# bbps.net
KiCad netlist of a schematic drawn in EAGLE
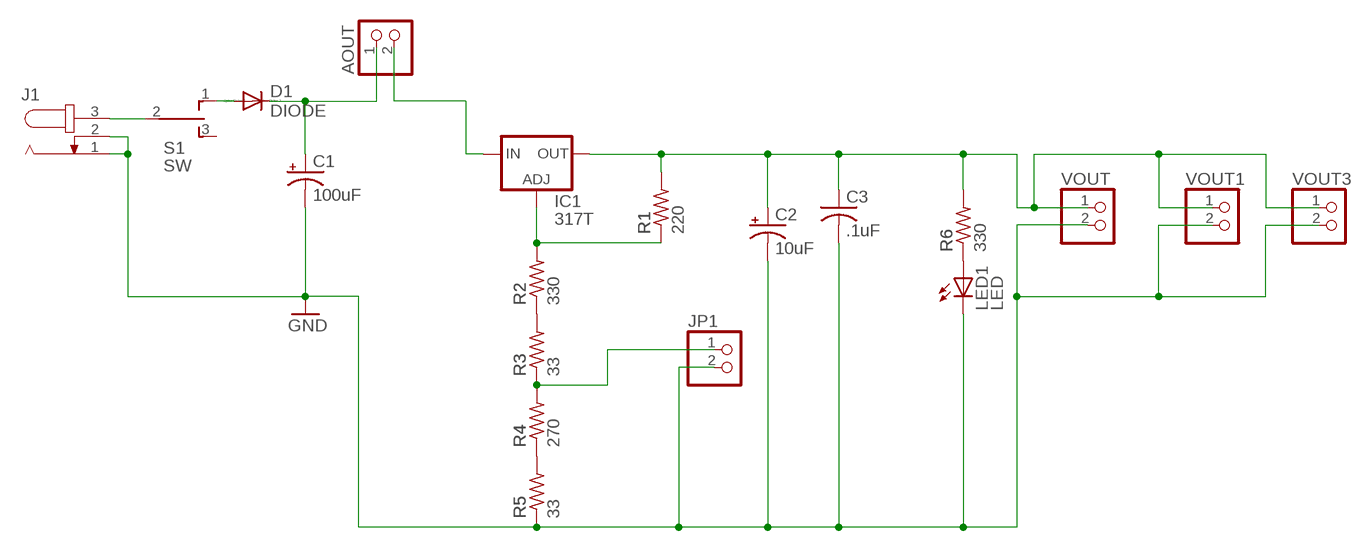
[diagram p0: schematic, sheet 1]

(export (version "E")
  (design (tool "Eeschema 10.0.6"))
  (components
    (comp (ref "AOUT")
      (value "PINHD-1X2")
      (footprint "eagle-import:1X02")
      (libsource (lib "eagle-import") (part "PINHD-1X2"))
    )
    (comp (ref "C1")
      (value "100uF")
      (footprint "eagle-import:CPOL_5MM")
      (libsource (lib "eagle-import") (part "CPOL5MM"))
    )
    (comp (ref "C2")
      (value "10uF")
      (footprint "eagle-import:CPOL_5MM")
      (libsource (lib "eagle-import") (part "CPOL5MM"))
    )
    (comp (ref "C3")
      (value ".1uF")
      (footprint "eagle-import:C050-024X044")
      (libsource (lib "eagle-import") (part "C-US050-024X044"))
    )
    (comp (ref "D1")
      (value "DIODE")
      (footprint "eagle-import:D40_10MM")
      (libsource (lib "eagle-import") (part "DIODE"))
    )
    (comp (ref "IC1")
      (value "317T")
      (footprint "eagle-import:317T")
      (libsource (lib "eagle-import") (part "317T"))
    )
    (comp (ref "J1")
      (value "JACK-PLUG0")
      (footprint "eagle-import:SPC4077")
      (libsource (lib "eagle-import") (part "JACK-PLUG0"))
    )
    (comp (ref "JP1")
      (value "PINHD-1X2")
      (footprint "eagle-import:1X02")
      (libsource (lib "eagle-import") (part "PINHD-1X2"))
    )
    (comp (ref "LED1")
      (value "LED")
      (footprint "eagle-import:LED_2.54MM")
      (libsource (lib "eagle-import") (part "LED"))
    )
    (comp (ref "R1")
      (value "220")
      (footprint "eagle-import:R207_7.6MM")
      (libsource (lib "eagle-import") (part "R"))
    )
    (comp (ref "R2")
      (value "330")
      (footprint "eagle-import:R207_7.6MM")
      (libsource (lib "eagle-import") (part "R"))
    )
    (comp (ref "R3")
      (value "33")
      (footprint "eagle-import:R207_7.6MM")
      (libsource (lib "eagle-import") (part "R"))
    )
    (comp (ref "R4")
      (value "270")
      (footprint "eagle-import:R207_7.6MM")
      (libsource (lib "eagle-import") (part "R"))
    )
    (comp (ref "R5")
      (value "33")
      (footprint "eagle-import:R207_7.6MM")
      (libsource (lib "eagle-import") (part "R"))
    )
    (comp (ref "R6")
      (value "330")
      (footprint "eagle-import:R207_7.6MM")
      (libsource (lib "eagle-import") (part "R"))
    )
    (comp (ref "S1")
      (value "SW")
      (footprint "eagle-import:SWITCH")
      (libsource (lib "eagle-import") (part "SWITCH"))
    )
    (comp (ref "VOUT")
      (value "PINHD-1X2")
      (footprint "eagle-import:1X02")
      (libsource (lib "eagle-import") (part "PINHD-1X2"))
    )
    (comp (ref "VOUT1")
      (value "PINHD-1X2")
      (footprint "eagle-import:1X02")
      (libsource (lib "eagle-import") (part "PINHD-1X2"))
    )
    (comp (ref "VOUT3")
      (value "PINHD-1X2")
      (footprint "eagle-import:1X02")
      (libsource (lib "eagle-import") (part "PINHD-1X2"))
    )
  )
  (nets
    (net (code "1") (name "GND") (class "Default")
      (node (ref "C1") (pin "-") (pinfunction "-_-") (pintype "passive"))
      (node (ref "C2") (pin "-") (pinfunction "-_-") (pintype "passive"))
      (node (ref "C3") (pin "2") (pinfunction "2_2") (pintype "passive"))
      (node (ref "J1") (pin "1") (pinfunction "1_1") (pintype "passive"))
      (node (ref "J1") (pin "2") (pinfunction "2_2") (pintype "passive"))
      (node (ref "JP1") (pin "2") (pinfunction "2_2") (pintype "passive"))
      (node (ref "LED1") (pin "K") (pinfunction "C_K") (pintype "passive"))
      (node (ref "R5") (pin "1") (pinfunction "1_1") (pintype "passive"))
      (node (ref "VOUT") (pin "2") (pinfunction "2_2") (pintype "passive"))
      (node (ref "VOUT1") (pin "2") (pinfunction "2_2") (pintype "passive"))
      (node (ref "VOUT3") (pin "2") (pinfunction "2_2") (pintype "passive"))
    )
    (net (code "2") (name "Net-(AOUT-Pad1)") (class "Default")
      (node (ref "AOUT") (pin "1") (pinfunction "1_1") (pintype "passive"))
      (node (ref "C1") (pin "+") (pinfunction "+_+") (pintype "passive"))
      (node (ref "D1") (pin "C") (pinfunction "C_C") (pintype "passive"))
    )
    (net (code "3") (name "Net-(D1-PadA)") (class "Default")
      (node (ref "D1") (pin "A") (pinfunction "A_A") (pintype "passive"))
      (node (ref "S1") (pin "1") (pinfunction "1_1") (pintype "passive"))
    )
    (net (code "4") (name "Net-(IC1-ADJ)") (class "Default")
      (node (ref "IC1") (pin "1") (pinfunction "ADJ_1") (pintype "input"))
      (node (ref "R1") (pin "1") (pinfunction "1_1") (pintype "passive"))
      (node (ref "R2") (pin "2") (pinfunction "2_2") (pintype "passive"))
    )
    (net (code "5") (name "Net-(IC1-IN)") (class "Default")
      (node (ref "AOUT") (pin "2") (pinfunction "2_2") (pintype "passive"))
      (node (ref "IC1") (pin "3") (pinfunction "IN_3") (pintype "input"))
    )
    (net (code "6") (name "Net-(IC1-OUT)") (class "Default")
      (node (ref "C2") (pin "+") (pinfunction "+_+") (pintype "passive"))
      (node (ref "C3") (pin "1") (pinfunction "1_1") (pintype "passive"))
      (node (ref "IC1") (pin "2") (pinfunction "OUT_2") (pintype "passive"))
      (node (ref "R1") (pin "2") (pinfunction "2_2") (pintype "passive"))
      (node (ref "R6") (pin "2") (pinfunction "2_2") (pintype "passive"))
      (node (ref "VOUT") (pin "1") (pinfunction "1_1") (pintype "passive"))
      (node (ref "VOUT1") (pin "1") (pinfunction "1_1") (pintype "passive"))
      (node (ref "VOUT3") (pin "1") (pinfunction "1_1") (pintype "passive"))
    )
    (net (code "7") (name "Net-(J1-Pad3)") (class "Default")
      (node (ref "J1") (pin "3") (pinfunction "3_3") (pintype "passive"))
      (node (ref "S1") (pin "2") (pinfunction "2_2") (pintype "passive"))
    )
    (net (code "8") (name "Net-(JP1-Pad1)") (class "Default")
      (node (ref "JP1") (pin "1") (pinfunction "1_1") (pintype "passive"))
      (node (ref "R3") (pin "1") (pinfunction "1_1") (pintype "passive"))
      (node (ref "R4") (pin "2") (pinfunction "2_2") (pintype "passive"))
    )
    (net (code "9") (name "Net-(LED1-PadA)") (class "Default")
      (node (ref "LED1") (pin "A") (pinfunction "A_A") (pintype "passive"))
      (node (ref "R6") (pin "1") (pinfunction "1_1") (pintype "passive"))
    )
    (net (code "10") (name "Net-(R2-Pad1)") (class "Default")
      (node (ref "R2") (pin "1") (pinfunction "1_1") (pintype "passive"))
      (node (ref "R3") (pin "2") (pinfunction "2_2") (pintype "passive"))
    )
    (net (code "11") (name "Net-(R4-Pad1)") (class "Default")
      (node (ref "R4") (pin "1") (pinfunction "1_1") (pintype "passive"))
      (node (ref "R5") (pin "2") (pinfunction "2_2") (pintype "passive"))
    )
    (net (code "12") (name "unconnected-(S1-Pad3)") (class "Default")
      (node (ref "S1") (pin "3") (pinfunction "3_3") (pintype "passive"))
    )
  )
)
